# AD6645.net
KiCad netlist of a schematic drawn in Altium Designer
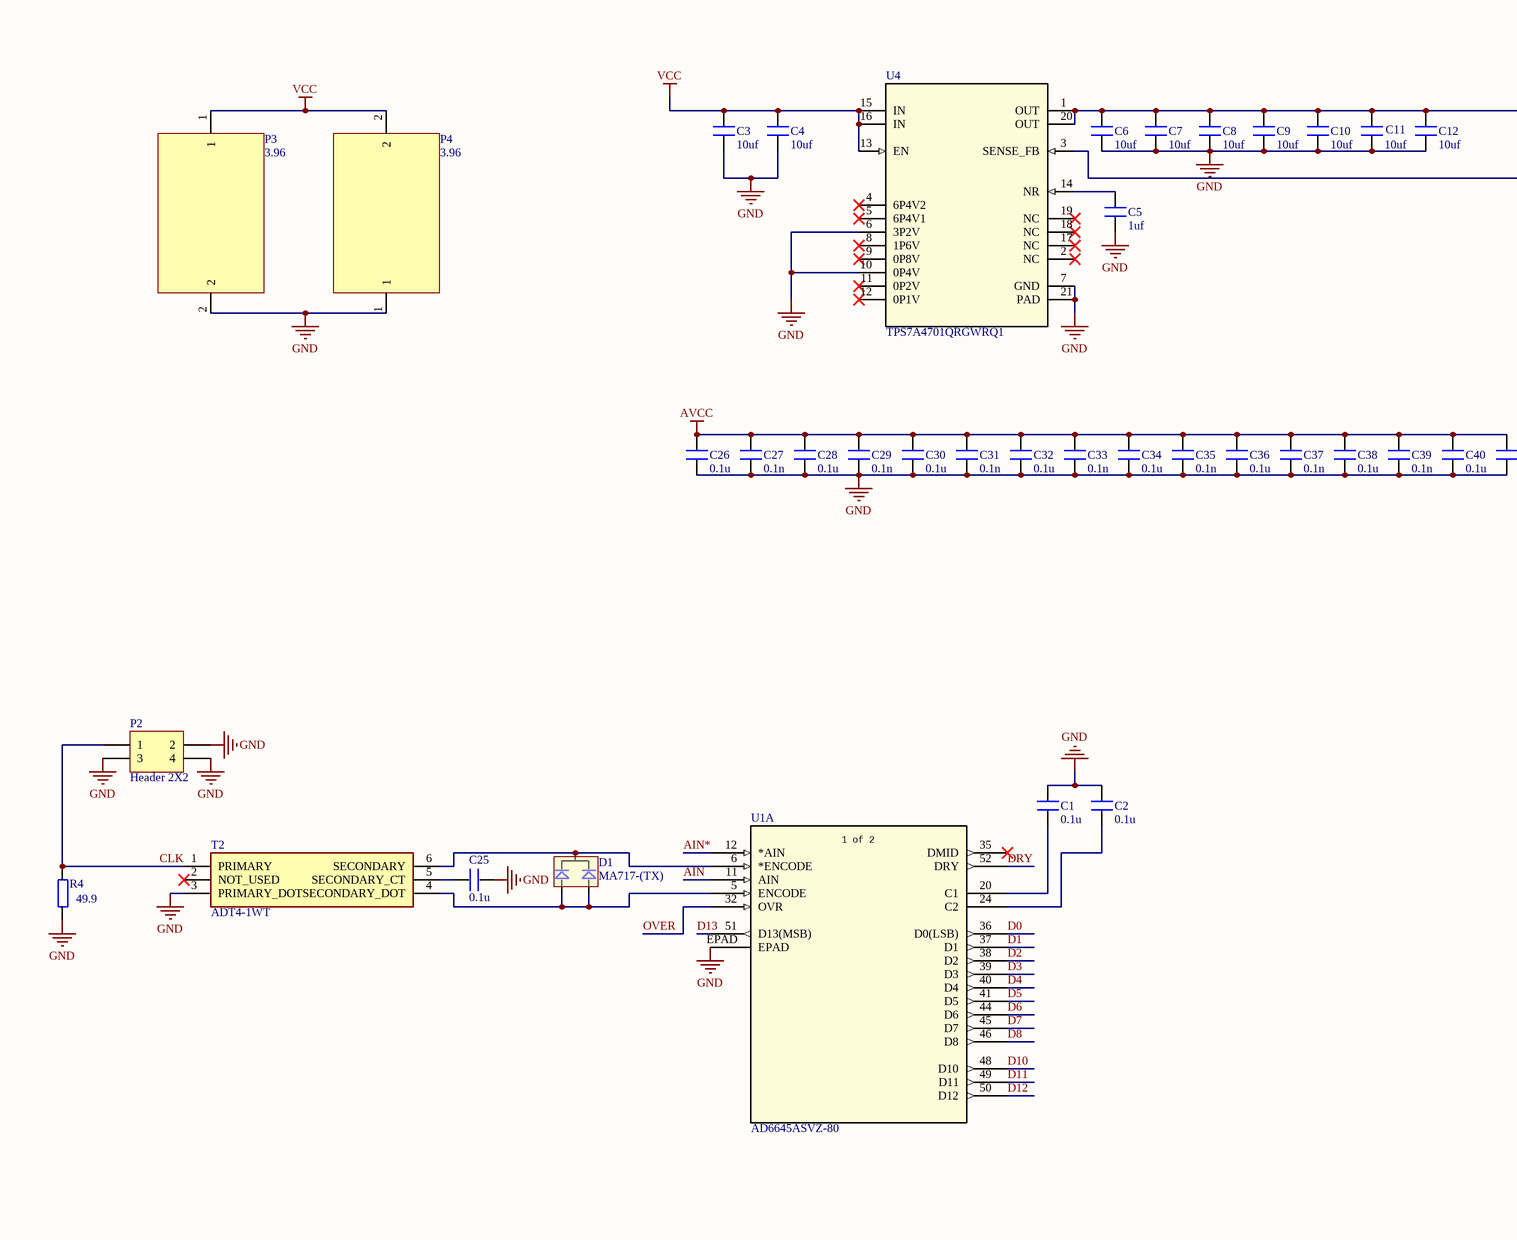
[diagram p0: AD6645.SchDoc, left]
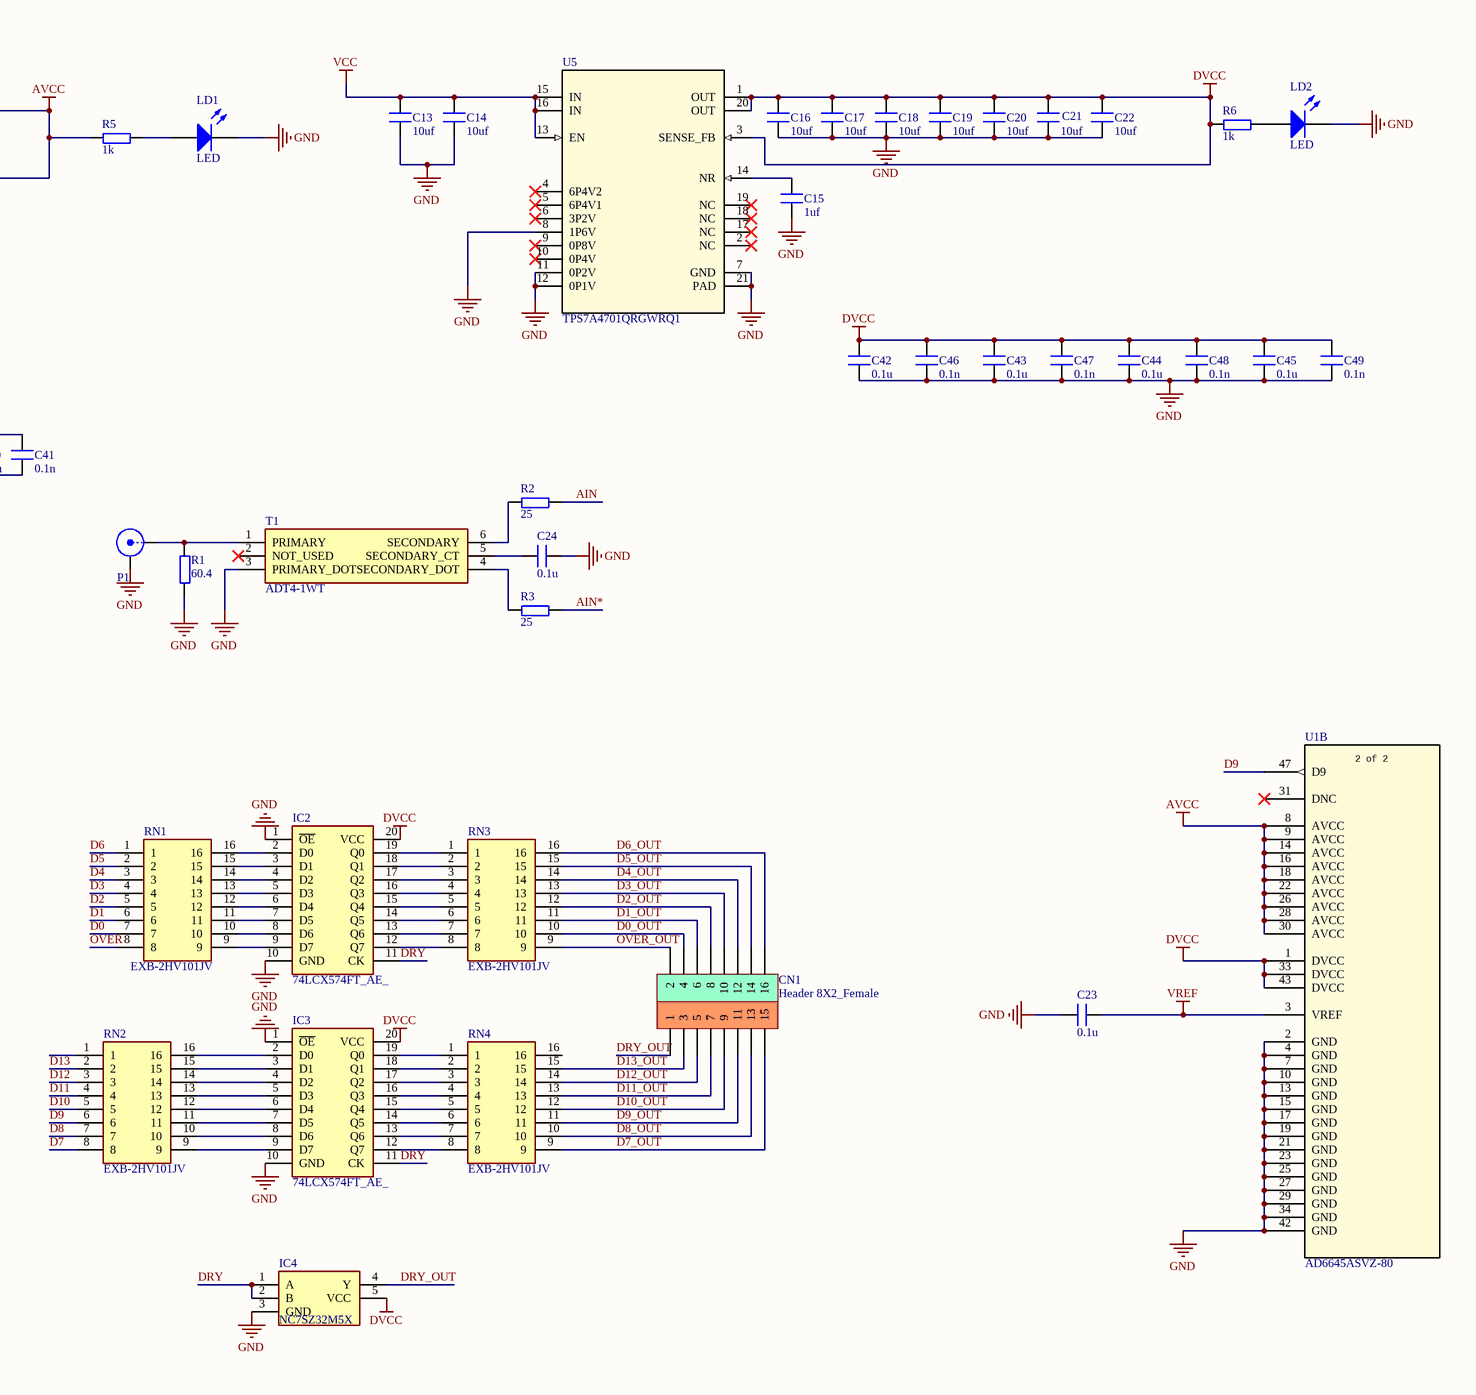
[diagram p1: AD6645.SchDoc, right]

(export (version "E")
  (design (tool "Eeschema 10.0.6"))
  (components
    (comp (ref "C1")
      (value "0.1u")
      (footprint "0402")
      (description "Capacitor")
      (libsource (lib "MYLIB") (part "C"))
    )
    (comp (ref "C2")
      (value "0.1u")
      (footprint "0402")
      (description "Capacitor")
      (libsource (lib "MYLIB") (part "C"))
    )
    (comp (ref "C3")
      (value "10uf")
      (footprint "0603C")
      (description "Capacitor")
      (libsource (lib "MYLIB") (part "C"))
    )
    (comp (ref "C4")
      (value "10uf")
      (footprint "0603C")
      (description "Capacitor")
      (libsource (lib "MYLIB") (part "C"))
    )
    (comp (ref "C5")
      (value "1uf")
      (footprint "0402")
      (description "Capacitor")
      (libsource (lib "MYLIB") (part "C"))
    )
    (comp (ref "C6")
      (value "10uf")
      (footprint "0603C")
      (description "Capacitor")
      (libsource (lib "MYLIB") (part "C"))
    )
    (comp (ref "C7")
      (value "10uf")
      (footprint "0603C")
      (description "Capacitor")
      (libsource (lib "MYLIB") (part "C"))
    )
    (comp (ref "C8")
      (value "10uf")
      (footprint "0603C")
      (description "Capacitor")
      (libsource (lib "MYLIB") (part "C"))
    )
    (comp (ref "C9")
      (value "10uf")
      (footprint "0603C")
      (description "Capacitor")
      (libsource (lib "MYLIB") (part "C"))
    )
    (comp (ref "C10")
      (value "10uf")
      (footprint "0603C")
      (description "Capacitor")
      (libsource (lib "MYLIB") (part "C"))
    )
    (comp (ref "C11")
      (value "10uf")
      (footprint "0603C")
      (description "Capacitor")
      (libsource (lib "MYLIB") (part "C"))
    )
    (comp (ref "C12")
      (value "10uf")
      (footprint "0603C")
      (description "Capacitor")
      (libsource (lib "MYLIB") (part "C"))
    )
    (comp (ref "C13")
      (value "10uf")
      (footprint "0603C")
      (description "Capacitor")
      (libsource (lib "MYLIB") (part "C"))
    )
    (comp (ref "C14")
      (value "10uf")
      (footprint "0603C")
      (description "Capacitor")
      (libsource (lib "MYLIB") (part "C"))
    )
    (comp (ref "C15")
      (value "1uf")
      (footprint "0402")
      (description "Capacitor")
      (libsource (lib "MYLIB") (part "C"))
    )
    (comp (ref "C16")
      (value "10uf")
      (footprint "0603C")
      (description "Capacitor")
      (libsource (lib "MYLIB") (part "C"))
    )
    (comp (ref "C17")
      (value "10uf")
      (footprint "0603C")
      (description "Capacitor")
      (libsource (lib "MYLIB") (part "C"))
    )
    (comp (ref "C18")
      (value "10uf")
      (footprint "0603C")
      (description "Capacitor")
      (libsource (lib "MYLIB") (part "C"))
    )
    (comp (ref "C19")
      (value "10uf")
      (footprint "0603C")
      (description "Capacitor")
      (libsource (lib "MYLIB") (part "C"))
    )
    (comp (ref "C20")
      (value "10uf")
      (footprint "0603C")
      (description "Capacitor")
      (libsource (lib "MYLIB") (part "C"))
    )
    (comp (ref "C21")
      (value "10uf")
      (footprint "0603C")
      (description "Capacitor")
      (libsource (lib "MYLIB") (part "C"))
    )
    (comp (ref "C22")
      (value "10uf")
      (footprint "0603C")
      (description "Capacitor")
      (libsource (lib "MYLIB") (part "C"))
    )
    (comp (ref "C23")
      (value "0.1u")
      (footprint "0402")
      (description "Capacitor")
      (libsource (lib "MYLIB") (part "C"))
    )
    (comp (ref "C24")
      (value "0.1u")
      (footprint "0603C")
      (description "Capacitor")
      (libsource (lib "MYLIB") (part "C"))
    )
    (comp (ref "C25")
      (value "0.1u")
      (footprint "0603C")
      (description "Capacitor")
      (libsource (lib "MYLIB") (part "C"))
    )
    (comp (ref "C26")
      (value "0.1u")
      (footprint "0402")
      (description "Capacitor")
      (libsource (lib "MYLIB") (part "C"))
    )
    (comp (ref "C27")
      (value "0.1n")
      (footprint "0402")
      (description "Capacitor")
      (libsource (lib "MYLIB") (part "C"))
    )
    (comp (ref "C28")
      (value "0.1u")
      (footprint "0402")
      (description "Capacitor")
      (libsource (lib "MYLIB") (part "C"))
    )
    (comp (ref "C29")
      (value "0.1n")
      (footprint "0402")
      (description "Capacitor")
      (libsource (lib "MYLIB") (part "C"))
    )
    (comp (ref "C30")
      (value "0.1u")
      (footprint "0402")
      (description "Capacitor")
      (libsource (lib "MYLIB") (part "C"))
    )
    (comp (ref "C31")
      (value "0.1n")
      (footprint "0402")
      (description "Capacitor")
      (libsource (lib "MYLIB") (part "C"))
    )
    (comp (ref "C32")
      (value "0.1u")
      (footprint "0402")
      (description "Capacitor")
      (libsource (lib "MYLIB") (part "C"))
    )
    (comp (ref "C33")
      (value "0.1n")
      (footprint "0402")
      (description "Capacitor")
      (libsource (lib "MYLIB") (part "C"))
    )
    (comp (ref "C34")
      (value "0.1u")
      (footprint "0402")
      (description "Capacitor")
      (libsource (lib "MYLIB") (part "C"))
    )
    (comp (ref "C35")
      (value "0.1n")
      (footprint "0402")
      (description "Capacitor")
      (libsource (lib "MYLIB") (part "C"))
    )
    (comp (ref "C36")
      (value "0.1u")
      (footprint "0402")
      (description "Capacitor")
      (libsource (lib "MYLIB") (part "C"))
    )
    (comp (ref "C37")
      (value "0.1n")
      (footprint "0402")
      (description "Capacitor")
      (libsource (lib "MYLIB") (part "C"))
    )
    (comp (ref "C38")
      (value "0.1u")
      (footprint "0402")
      (description "Capacitor")
      (libsource (lib "MYLIB") (part "C"))
    )
    (comp (ref "C39")
      (value "0.1n")
      (footprint "0402")
      (description "Capacitor")
      (libsource (lib "MYLIB") (part "C"))
    )
    (comp (ref "C40")
      (value "0.1u")
      (footprint "0402")
      (description "Capacitor")
      (libsource (lib "MYLIB") (part "C"))
    )
    (comp (ref "C41")
      (value "0.1n")
      (footprint "0402")
      (description "Capacitor")
      (libsource (lib "MYLIB") (part "C"))
    )
    (comp (ref "C42")
      (value "0.1u")
      (footprint "0402")
      (description "Capacitor")
      (libsource (lib "MYLIB") (part "C"))
    )
    (comp (ref "C43")
      (value "0.1u")
      (footprint "0402")
      (description "Capacitor")
      (libsource (lib "MYLIB") (part "C"))
    )
    (comp (ref "C44")
      (value "0.1u")
      (footprint "0402")
      (description "Capacitor")
      (libsource (lib "MYLIB") (part "C"))
    )
    (comp (ref "C45")
      (value "0.1u")
      (footprint "0402")
      (description "Capacitor")
      (libsource (lib "MYLIB") (part "C"))
    )
    (comp (ref "C46")
      (value "0.1n")
      (footprint "0402")
      (description "Capacitor")
      (libsource (lib "MYLIB") (part "C"))
    )
    (comp (ref "C47")
      (value "0.1n")
      (footprint "0402")
      (description "Capacitor")
      (libsource (lib "MYLIB") (part "C"))
    )
    (comp (ref "C48")
      (value "0.1n")
      (footprint "0402")
      (description "Capacitor")
      (libsource (lib "MYLIB") (part "C"))
    )
    (comp (ref "C49")
      (value "0.1n")
      (footprint "0402")
      (description "Capacitor")
      (libsource (lib "MYLIB") (part "C"))
    )
    (comp (ref "CN1")
      (value "Header 8X2_Female")
      (footprint "HDR_8x2_2R54_V_F")
      (description "Header, 8-Pin, Dual row,female")
      (fields (field (name "PUBLISHER") "Altium Limited"))
      (libsource (lib "MYLIB") (part "Header 8X2_Female"))
    )
    (comp (ref "D1")
      (value "MA717-(TX)")
      (footprint "SOT-23")
      (description "双肖特基二极管")
      (libsource (lib "MYLIB") (part "BAT54C"))
    )
    (comp (ref "IC2")
      (value "74LCX574FT_AE_")
      (footprint "MYLIB:SOP65P640X120-20N")
      (description "Integrated Circuit")
      (fields (field (name "MANUFACTURER_PART_NUMBER") "74LCX574FT(AE)"))
      (libsource (lib "*") (part "74LCX574FT_AE_"))
    )
    (comp (ref "IC3")
      (value "74LCX574FT_AE_")
      (footprint "MYLIB:SOP65P640X120-20N")
      (description "Integrated Circuit")
      (fields (field (name "MANUFACTURER_PART_NUMBER") "74LCX574FT(AE)"))
      (libsource (lib "MYLIB") (part "74LCX574FT_AE_"))
    )
    (comp (ref "IC4")
      (value "NC7SZ32M5X")
      (footprint "MYLIB:SOT95P280X145-5N")
      (description "Integrated Circuit")
      (fields (field (name "MOUSER PART NUMBER") "512-NC7SZ32M5X"))
      (libsource (lib "*") (part "NC7SZ32M5X"))
    )
    (comp (ref "LD1")
      (value "LED")
      (footprint "SMDLED")
      (description "Typical RED, GREEN, YELLOW, AMBER GaAs LED")
      (fields (field (name "PUBLISHER") "Altium Limited"))
      (libsource (lib "MYLIB") (part "LED"))
    )
    (comp (ref "LD2")
      (value "LED")
      (footprint "SMDLED")
      (description "Typical RED, GREEN, YELLOW, AMBER GaAs LED")
      (fields (field (name "PUBLISHER") "Altium Limited"))
      (libsource (lib "MYLIB") (part "LED"))
    )
    (comp (ref "P1")
      (value "SMA")
      (footprint "SMA")
      (description "SMA Connector")
      (libsource (lib "MYLIB") (part "SMA"))
    )
    (comp (ref "P2")
      (value "Header 2X2")
      (footprint "HDR2X2")
      (description "Header, 2-Pin, Dual row")
      (fields (field (name "PUBLISHER") "Altium Limited"))
      (libsource (lib "MYLIB") (part "Header 2X2"))
    )
    (comp (ref "P3") (value "3.96") (footprint "3.96") (libsource (lib "MYLIB") (part "3.96")))
    (comp (ref "P4") (value "3.96") (footprint "3.96") (libsource (lib "") (part "3.96_1")))
    (comp (ref "R1")
      (value "60.4")
      (footprint "0603R")
      (description "Resistor")
      (libsource (lib "MYLIB") (part "Resistor"))
    )
    (comp (ref "R2")
      (value "25")
      (footprint "0603R")
      (description "Resistor")
      (libsource (lib "MYLIB") (part "Resistor"))
    )
    (comp (ref "R3")
      (value "25")
      (footprint "0603R")
      (description "Resistor")
      (libsource (lib "MYLIB") (part "Resistor"))
    )
    (comp (ref "R4")
      (value "49.9")
      (footprint "0603R")
      (description "Resistor")
      (libsource (lib "MYLIB") (part "Resistor"))
    )
    (comp (ref "R5")
      (value "1k")
      (footprint "0603R")
      (description "Resistor")
      (libsource (lib "MYLIB") (part "Resistor"))
    )
    (comp (ref "R6")
      (value "1k")
      (footprint "0603R")
      (description "Resistor")
      (libsource (lib "MYLIB") (part "Resistor"))
    )
    (comp (ref "RN1")
      (value "EXB-2HV101JV")
      (footprint "MYLIB:EXB2HV101JV")
      (description "Resistor Network")
      (fields (field (name "MOUSER PART NUMBER") "667-EXB-2HV101JV"))
      (libsource (lib "*") (part "EXB-2HV101JV"))
    )
    (comp (ref "RN2")
      (value "EXB-2HV101JV")
      (footprint "MYLIB:EXB2HV101JV")
      (description "Resistor Network")
      (fields (field (name "MOUSER PART NUMBER") "667-EXB-2HV101JV"))
      (libsource (lib "MYLIB") (part "EXB-2HV101JV"))
    )
    (comp (ref "RN3")
      (value "EXB-2HV101JV")
      (footprint "MYLIB:EXB2HV101JV")
      (description "Resistor Network")
      (fields (field (name "MOUSER PART NUMBER") "667-EXB-2HV101JV"))
      (libsource (lib "MYLIB") (part "EXB-2HV101JV"))
    )
    (comp (ref "RN4")
      (value "EXB-2HV101JV")
      (footprint "MYLIB:EXB2HV101JV")
      (description "Resistor Network")
      (fields (field (name "MOUSER PART NUMBER") "667-EXB-2HV101JV"))
      (libsource (lib "MYLIB") (part "EXB-2HV101JV"))
    )
    (comp (ref "T1")
      (value "ADT4-1WT")
      (footprint "MYLIB:ADT41WT")
      (description "Transformer")
      (libsource (lib "*") (part "ADT4-1WT"))
    )
    (comp (ref "T2")
      (value "ADT4-1WT")
      (footprint "MYLIB:ADT41WT")
      (description "Transformer")
      (libsource (lib "MYLIB") (part "ADT4-1WT"))
    )
    (comp (ref "U1")
      (value "AD6645ASVZ-80")
      (footprint "SV_52_1_ADI")
      (description "No Description Available")
      (fields (field (name "COPYRIGHT") "Copyright (C) 2021 Accelerated Designs. All rights reserved"))
      (libsource (lib "MYLIB") (part "AD6645ASVZ-80"))
    )
    (comp (ref "U4")
      (value "TPS7A4701QRGWRQ1")
      (footprint "RGW0020A")
      (description "No Description Available")
      (fields
        (field (name "MANUFACTURER") "Texas Instruments")
        (field (name "COPYRIGHT") "Copyright (C) 2018 Accelerated Designs. All rights reserved")
      )
      (libsource (lib "MYLIB") (part "TPS7A4701QRGWRQ1"))
    )
    (comp (ref "U5")
      (value "TPS7A4701QRGWRQ1")
      (footprint "RGW0020A")
      (description "No Description Available")
      (fields
        (field (name "MANUFACTURER") "Texas Instruments")
        (field (name "COPYRIGHT") "Copyright (C) 2018 Accelerated Designs. All rights reserved")
      )
      (libsource (lib "MYLIB") (part "TPS7A4701QRGWRQ1"))
    )
  )
  (nets
    (net (code "1") (name "/AIN") (class "Default")
      (node (ref "R2") (pin "2") (pintype "passive"))
      (node (ref "U1") (pin "11") (pinfunction "AIN_11") (pintype "input"))
    )
    (net (code "2") (name "/AIN*") (class "Default")
      (node (ref "R3") (pin "2") (pintype "passive"))
      (node (ref "U1") (pin "12") (pinfunction "*AIN_12") (pintype "input"))
    )
    (net (code "3") (name "/CLK") (class "Default")
      (node (ref "P2") (pin "1") (pinfunction "1_1") (pintype "passive"))
      (node (ref "R4") (pin "2") (pintype "passive"))
      (node (ref "T2") (pin "1") (pinfunction "PRIMARY_1") (pintype "passive"))
    )
    (net (code "4") (name "/D0") (class "Default")
      (node (ref "RN1") (pin "7") (pinfunction "7_7") (pintype "passive"))
      (node (ref "U1") (pin "36") (pinfunction "D0(LSB)_36") (pintype "output"))
    )
    (net (code "5") (name "/D0_OUT") (class "Default")
      (node (ref "CN1") (pin "4") (pinfunction "4_4") (pintype "passive"))
      (node (ref "RN3") (pin "10") (pinfunction "10_10") (pintype "passive"))
    )
    (net (code "6") (name "/D1") (class "Default")
      (node (ref "RN1") (pin "6") (pinfunction "6_6") (pintype "passive"))
      (node (ref "U1") (pin "37") (pinfunction "D1_37") (pintype "output"))
    )
    (net (code "7") (name "/D1_OUT") (class "Default")
      (node (ref "CN1") (pin "6") (pinfunction "6_6") (pintype "passive"))
      (node (ref "RN3") (pin "11") (pinfunction "11_11") (pintype "passive"))
    )
    (net (code "8") (name "/D2") (class "Default")
      (node (ref "RN1") (pin "5") (pinfunction "5_5") (pintype "passive"))
      (node (ref "U1") (pin "38") (pinfunction "D2_38") (pintype "output"))
    )
    (net (code "9") (name "/D2_OUT") (class "Default")
      (node (ref "CN1") (pin "8") (pinfunction "8_8") (pintype "passive"))
      (node (ref "RN3") (pin "12") (pinfunction "12_12") (pintype "passive"))
    )
    (net (code "10") (name "/D3") (class "Default")
      (node (ref "RN1") (pin "4") (pinfunction "4_4") (pintype "passive"))
      (node (ref "U1") (pin "39") (pinfunction "D3_39") (pintype "output"))
    )
    (net (code "11") (name "/D3_OUT") (class "Default")
      (node (ref "CN1") (pin "10") (pinfunction "10_10") (pintype "passive"))
      (node (ref "RN3") (pin "13") (pinfunction "13_13") (pintype "passive"))
    )
    (net (code "12") (name "/D4") (class "Default")
      (node (ref "RN1") (pin "3") (pinfunction "3_3") (pintype "passive"))
      (node (ref "U1") (pin "40") (pinfunction "D4_40") (pintype "output"))
    )
    (net (code "13") (name "/D4_OUT") (class "Default")
      (node (ref "CN1") (pin "12") (pinfunction "12_12") (pintype "passive"))
      (node (ref "RN3") (pin "14") (pinfunction "14_14") (pintype "passive"))
    )
    (net (code "14") (name "/D5") (class "Default")
      (node (ref "RN1") (pin "2") (pinfunction "2_2") (pintype "passive"))
      (node (ref "U1") (pin "41") (pinfunction "D5_41") (pintype "output"))
    )
    (net (code "15") (name "/D5_OUT") (class "Default")
      (node (ref "CN1") (pin "14") (pinfunction "14_14") (pintype "passive"))
      (node (ref "RN3") (pin "15") (pinfunction "15_15") (pintype "passive"))
    )
    (net (code "16") (name "/D6") (class "Default")
      (node (ref "RN1") (pin "1") (pinfunction "1_1") (pintype "passive"))
      (node (ref "U1") (pin "44") (pinfunction "D6_44") (pintype "output"))
    )
    (net (code "17") (name "/D6_OUT") (class "Default")
      (node (ref "CN1") (pin "16") (pinfunction "16_16") (pintype "passive"))
      (node (ref "RN3") (pin "16") (pinfunction "16_16") (pintype "passive"))
    )
    (net (code "18") (name "/D7") (class "Default")
      (node (ref "RN2") (pin "8") (pinfunction "8_8") (pintype "passive"))
      (node (ref "U1") (pin "45") (pinfunction "D7_45") (pintype "output"))
    )
    (net (code "19") (name "/D7_OUT") (class "Default")
      (node (ref "CN1") (pin "15") (pinfunction "15_15") (pintype "passive"))
      (node (ref "RN4") (pin "9") (pinfunction "9_9") (pintype "passive"))
    )
    (net (code "20") (name "/D8") (class "Default")
      (node (ref "RN2") (pin "7") (pinfunction "7_7") (pintype "passive"))
      (node (ref "U1") (pin "46") (pinfunction "D8_46") (pintype "output"))
    )
    (net (code "21") (name "/D8_OUT") (class "Default")
      (node (ref "CN1") (pin "13") (pinfunction "13_13") (pintype "passive"))
      (node (ref "RN4") (pin "10") (pinfunction "10_10") (pintype "passive"))
    )
    (net (code "22") (name "/D9") (class "Default")
      (node (ref "RN2") (pin "6") (pinfunction "6_6") (pintype "passive"))
      (node (ref "U1") (pin "47") (pinfunction "D9_47") (pintype "output"))
    )
    (net (code "23") (name "/D9_OUT") (class "Default")
      (node (ref "CN1") (pin "11") (pinfunction "11_11") (pintype "passive"))
      (node (ref "RN4") (pin "11") (pinfunction "11_11") (pintype "passive"))
    )
    (net (code "24") (name "/D10") (class "Default")
      (node (ref "RN2") (pin "5") (pinfunction "5_5") (pintype "passive"))
      (node (ref "U1") (pin "48") (pinfunction "D10_48") (pintype "output"))
    )
    (net (code "25") (name "/D10_OUT") (class "Default")
      (node (ref "CN1") (pin "9") (pinfunction "9_9") (pintype "passive"))
      (node (ref "RN4") (pin "12") (pinfunction "12_12") (pintype "passive"))
    )
    (net (code "26") (name "/D11") (class "Default")
      (node (ref "RN2") (pin "4") (pinfunction "4_4") (pintype "passive"))
      (node (ref "U1") (pin "49") (pinfunction "D11_49") (pintype "output"))
    )
    (net (code "27") (name "/D11_OUT") (class "Default")
      (node (ref "CN1") (pin "7") (pinfunction "7_7") (pintype "passive"))
      (node (ref "RN4") (pin "13") (pinfunction "13_13") (pintype "passive"))
    )
    (net (code "28") (name "/D12") (class "Default")
      (node (ref "RN2") (pin "3") (pinfunction "3_3") (pintype "passive"))
      (node (ref "U1") (pin "50") (pinfunction "D12_50") (pintype "output"))
    )
    (net (code "29") (name "/D12_OUT") (class "Default")
      (node (ref "CN1") (pin "5") (pinfunction "5_5") (pintype "passive"))
      (node (ref "RN4") (pin "14") (pinfunction "14_14") (pintype "passive"))
    )
    (net (code "30") (name "/D13") (class "Default")
      (node (ref "RN2") (pin "2") (pinfunction "2_2") (pintype "passive"))
      (node (ref "U1") (pin "51") (pinfunction "D13(MSB)_51") (pintype "output"))
    )
    (net (code "31") (name "/D13_OUT") (class "Default")
      (node (ref "CN1") (pin "3") (pinfunction "3_3") (pintype "passive"))
      (node (ref "RN4") (pin "15") (pinfunction "15_15") (pintype "passive"))
    )
    (net (code "32") (name "/DRY") (class "Default")
      (node (ref "IC2") (pin "11") (pinfunction "CK_11") (pintype "passive"))
      (node (ref "IC3") (pin "11") (pinfunction "CK_11") (pintype "passive"))
      (node (ref "IC4") (pin "1") (pinfunction "A_1") (pintype "passive"))
      (node (ref "IC4") (pin "2") (pinfunction "B_2") (pintype "passive"))
      (node (ref "U1") (pin "52") (pinfunction "DRY_52") (pintype "output"))
    )
    (net (code "33") (name "/DRY_OUT") (class "Default")
      (node (ref "CN1") (pin "1") (pinfunction "1_1") (pintype "passive"))
      (node (ref "IC4") (pin "4") (pinfunction "Y_4") (pintype "passive"))
    )
    (net (code "34") (name "/OVER") (class "Default")
      (node (ref "RN1") (pin "8") (pinfunction "8_8") (pintype "passive"))
      (node (ref "U1") (pin "32") (pinfunction "OVR_32") (pintype "input"))
    )
    (net (code "35") (name "/OVER_OUT") (class "Default")
      (node (ref "CN1") (pin "2") (pinfunction "2_2") (pintype "passive"))
      (node (ref "RN3") (pin "9") (pinfunction "9_9") (pintype "passive"))
    )
    (net (code "36") (name "AVCC") (class "Default")
      (node (ref "C10") (pin "2") (pintype "passive"))
      (node (ref "C11") (pin "2") (pintype "passive"))
      (node (ref "C12") (pin "2") (pintype "passive"))
      (node (ref "C26") (pin "2") (pintype "passive"))
      (node (ref "C27") (pin "2") (pintype "passive"))
      (node (ref "C28") (pin "2") (pintype "passive"))
      (node (ref "C29") (pin "2") (pintype "passive"))
      (node (ref "C30") (pin "2") (pintype "passive"))
      (node (ref "C31") (pin "2") (pintype "passive"))
      (node (ref "C32") (pin "2") (pintype "passive"))
      (node (ref "C33") (pin "2") (pintype "passive"))
      (node (ref "C34") (pin "2") (pintype "passive"))
      (node (ref "C35") (pin "2") (pintype "passive"))
      (node (ref "C36") (pin "2") (pintype "passive"))
      (node (ref "C37") (pin "2") (pintype "passive"))
      (node (ref "C38") (pin "2") (pintype "passive"))
      (node (ref "C39") (pin "2") (pintype "passive"))
      (node (ref "C40") (pin "2") (pintype "passive"))
      (node (ref "C41") (pin "2") (pintype "passive"))
      (node (ref "C6") (pin "2") (pintype "passive"))
      (node (ref "C7") (pin "2") (pintype "passive"))
      (node (ref "C8") (pin "2") (pintype "passive"))
      (node (ref "C9") (pin "2") (pintype "passive"))
      (node (ref "R5") (pin "1") (pintype "passive"))
      (node (ref "U1") (pin "14") (pinfunction "AVCC_14") (pintype "power_in"))
      (node (ref "U1") (pin "16") (pinfunction "AVCC_16") (pintype "power_in"))
      (node (ref "U1") (pin "18") (pinfunction "AVCC_18") (pintype "power_in"))
      (node (ref "U1") (pin "22") (pinfunction "AVCC_22") (pintype "power_in"))
      (node (ref "U1") (pin "26") (pinfunction "AVCC_26") (pintype "power_in"))
      (node (ref "U1") (pin "28") (pinfunction "AVCC_28") (pintype "power_in"))
      (node (ref "U1") (pin "30") (pinfunction "AVCC_30") (pintype "power_in"))
      (node (ref "U1") (pin "8") (pinfunction "AVCC_8") (pintype "power_in"))
      (node (ref "U1") (pin "9") (pinfunction "AVCC_9") (pintype "power_in"))
      (node (ref "U4") (pin "1") (pinfunction "OUT_1") (pintype "power_in"))
      (node (ref "U4") (pin "20") (pinfunction "OUT_20") (pintype "power_in"))
      (node (ref "U4") (pin "3") (pinfunction "SENSE_FB_3") (pintype "input"))
    )
    (net (code "37") (name "DVCC") (class "Default")
      (node (ref "C16") (pin "2") (pintype "passive"))
      (node (ref "C17") (pin "2") (pintype "passive"))
      (node (ref "C18") (pin "2") (pintype "passive"))
      (node (ref "C19") (pin "2") (pintype "passive"))
      (node (ref "C20") (pin "2") (pintype "passive"))
      (node (ref "C21") (pin "2") (pintype "passive"))
      (node (ref "C22") (pin "2") (pintype "passive"))
      (node (ref "C42") (pin "2") (pintype "passive"))
      (node (ref "C43") (pin "2") (pintype "passive"))
      (node (ref "C44") (pin "2") (pintype "passive"))
      (node (ref "C45") (pin "2") (pintype "passive"))
      (node (ref "C46") (pin "2") (pintype "passive"))
      (node (ref "C47") (pin "2") (pintype "passive"))
      (node (ref "C48") (pin "2") (pintype "passive"))
      (node (ref "C49") (pin "2") (pintype "passive"))
      (node (ref "IC2") (pin "20") (pinfunction "VCC_20") (pintype "passive"))
      (node (ref "IC3") (pin "20") (pinfunction "VCC_20") (pintype "passive"))
      (node (ref "IC4") (pin "5") (pinfunction "VCC_5") (pintype "power_in"))
      (node (ref "R6") (pin "1") (pintype "passive"))
      (node (ref "U1") (pin "1") (pinfunction "DVCC_1") (pintype "power_in"))
      (node (ref "U1") (pin "33") (pinfunction "DVCC_33") (pintype "power_in"))
      (node (ref "U1") (pin "43") (pinfunction "DVCC_43") (pintype "power_in"))
      (node (ref "U5") (pin "1") (pinfunction "OUT_1") (pintype "power_in"))
      (node (ref "U5") (pin "20") (pinfunction "OUT_20") (pintype "power_in"))
      (node (ref "U5") (pin "3") (pinfunction "SENSE_FB_3") (pintype "input"))
    )
    (net (code "38") (name "GND") (class "Default")
      (node (ref "C1") (pin "2") (pintype "passive"))
      (node (ref "C10") (pin "1") (pintype "passive"))
      (node (ref "C11") (pin "1") (pintype "passive"))
      (node (ref "C12") (pin "1") (pintype "passive"))
      (node (ref "C13") (pin "1") (pintype "passive"))
      (node (ref "C14") (pin "1") (pintype "passive"))
      (node (ref "C15") (pin "1") (pintype "passive"))
      (node (ref "C16") (pin "1") (pintype "passive"))
      (node (ref "C17") (pin "1") (pintype "passive"))
      (node (ref "C18") (pin "1") (pintype "passive"))
      (node (ref "C19") (pin "1") (pintype "passive"))
      (node (ref "C2") (pin "2") (pintype "passive"))
      (node (ref "C20") (pin "1") (pintype "passive"))
      (node (ref "C21") (pin "1") (pintype "passive"))
      (node (ref "C22") (pin "1") (pintype "passive"))
      (node (ref "C23") (pin "1") (pintype "passive"))
      (node (ref "C24") (pin "2") (pintype "passive"))
      (node (ref "C25") (pin "2") (pintype "passive"))
      (node (ref "C26") (pin "1") (pintype "passive"))
      (node (ref "C27") (pin "1") (pintype "passive"))
      (node (ref "C28") (pin "1") (pintype "passive"))
      (node (ref "C29") (pin "1") (pintype "passive"))
      (node (ref "C3") (pin "1") (pintype "passive"))
      (node (ref "C30") (pin "1") (pintype "passive"))
      (node (ref "C31") (pin "1") (pintype "passive"))
      (node (ref "C32") (pin "1") (pintype "passive"))
      (node (ref "C33") (pin "1") (pintype "passive"))
      (node (ref "C34") (pin "1") (pintype "passive"))
      (node (ref "C35") (pin "1") (pintype "passive"))
      (node (ref "C36") (pin "1") (pintype "passive"))
      (node (ref "C37") (pin "1") (pintype "passive"))
      (node (ref "C38") (pin "1") (pintype "passive"))
      (node (ref "C39") (pin "1") (pintype "passive"))
      (node (ref "C4") (pin "1") (pintype "passive"))
      (node (ref "C40") (pin "1") (pintype "passive"))
      (node (ref "C41") (pin "1") (pintype "passive"))
      (node (ref "C42") (pin "1") (pintype "passive"))
      (node (ref "C43") (pin "1") (pintype "passive"))
      (node (ref "C44") (pin "1") (pintype "passive"))
      (node (ref "C45") (pin "1") (pintype "passive"))
      (node (ref "C46") (pin "1") (pintype "passive"))
      (node (ref "C47") (pin "1") (pintype "passive"))
      (node (ref "C48") (pin "1") (pintype "passive"))
      (node (ref "C49") (pin "1") (pintype "passive"))
      (node (ref "C5") (pin "1") (pintype "passive"))
      (node (ref "C6") (pin "1") (pintype "passive"))
      (node (ref "C7") (pin "1") (pintype "passive"))
      (node (ref "C8") (pin "1") (pintype "passive"))
      (node (ref "C9") (pin "1") (pintype "passive"))
      (node (ref "IC2") (pin "1") (pinfunction "~{OE}_1") (pintype "passive"))
      (node (ref "IC2") (pin "10") (pinfunction "GND_10") (pintype "passive"))
      (node (ref "IC3") (pin "1") (pinfunction "~{OE}_1") (pintype "passive"))
      (node (ref "IC3") (pin "10") (pinfunction "GND_10") (pintype "passive"))
      (node (ref "IC4") (pin "3") (pinfunction "GND_3") (pintype "power_in"))
      (node (ref "LD1") (pin "2") (pinfunction "K_2") (pintype "passive"))
      (node (ref "LD2") (pin "2") (pinfunction "K_2") (pintype "passive"))
      (node (ref "P1") (pin "2") (pinfunction "Y_2") (pintype "passive"))
      (node (ref "P2") (pin "2") (pinfunction "2_2") (pintype "passive"))
      (node (ref "P2") (pin "3") (pinfunction "3_3") (pintype "passive"))
      (node (ref "P2") (pin "4") (pinfunction "4_4") (pintype "passive"))
      (node (ref "P3") (pin "2") (pinfunction "2_2") (pintype "passive"))
      (node (ref "P4") (pin "1") (pinfunction "1_1") (pintype "passive"))
      (node (ref "R1") (pin "1") (pintype "passive"))
      (node (ref "R4") (pin "1") (pintype "passive"))
      (node (ref "T1") (pin "3") (pinfunction "PRIMARY_DOT_3") (pintype "passive"))
      (node (ref "T2") (pin "3") (pinfunction "PRIMARY_DOT_3") (pintype "passive"))
      (node (ref "U1") (pin "10") (pinfunction "GND_10") (pintype "power_in"))
      (node (ref "U1") (pin "13") (pinfunction "GND_13") (pintype "power_in"))
      (node (ref "U1") (pin "15") (pinfunction "GND_15") (pintype "power_in"))
      (node (ref "U1") (pin "17") (pinfunction "GND_17") (pintype "power_in"))
      (node (ref "U1") (pin "19") (pinfunction "GND_19") (pintype "power_in"))
      (node (ref "U1") (pin "2") (pinfunction "GND_2") (pintype "power_in"))
      (node (ref "U1") (pin "21") (pinfunction "GND_21") (pintype "power_in"))
      (node (ref "U1") (pin "23") (pinfunction "GND_23") (pintype "power_in"))
      (node (ref "U1") (pin "25") (pinfunction "GND_25") (pintype "power_in"))
      (node (ref "U1") (pin "27") (pinfunction "GND_27") (pintype "power_in"))
      (node (ref "U1") (pin "29") (pinfunction "GND_29") (pintype "power_in"))
      (node (ref "U1") (pin "34") (pinfunction "GND_34") (pintype "power_in"))
      (node (ref "U1") (pin "4") (pinfunction "GND_4") (pintype "power_in"))
      (node (ref "U1") (pin "42") (pinfunction "GND_42") (pintype "power_in"))
      (node (ref "U1") (pin "7") (pinfunction "GND_7") (pintype "power_in"))
      (node (ref "U1") (pin "EPAD") (pinfunction "EPAD_EPAD") (pintype "passive"))
      (node (ref "U4") (pin "10") (pinfunction "0P4V_10") (pintype "passive"))
      (node (ref "U4") (pin "21") (pinfunction "PAD_21") (pintype "passive"))
      (node (ref "U4") (pin "6") (pinfunction "3P2V_6") (pintype "passive"))
      (node (ref "U4") (pin "7") (pinfunction "GND_7") (pintype "power_in"))
      (node (ref "U5") (pin "11") (pinfunction "0P2V_11") (pintype "passive"))
      (node (ref "U5") (pin "12") (pinfunction "0P1V_12") (pintype "passive"))
      (node (ref "U5") (pin "21") (pinfunction "PAD_21") (pintype "passive"))
      (node (ref "U5") (pin "7") (pinfunction "GND_7") (pintype "power_in"))
      (node (ref "U5") (pin "8") (pinfunction "1P6V_8") (pintype "passive"))
    )
    (net (code "39") (name "Net-(IC2-D0)") (class "Default")
      (node (ref "IC2") (pin "2") (pinfunction "D0_2") (pintype "passive"))
      (node (ref "RN1") (pin "16") (pinfunction "16_16") (pintype "passive"))
    )
    (net (code "40") (name "Net-(IC2-D1)") (class "Default")
      (node (ref "IC2") (pin "3") (pinfunction "D1_3") (pintype "passive"))
      (node (ref "RN1") (pin "15") (pinfunction "15_15") (pintype "passive"))
    )
    (net (code "41") (name "Net-(IC2-D2)") (class "Default")
      (node (ref "IC2") (pin "4") (pinfunction "D2_4") (pintype "passive"))
      (node (ref "RN1") (pin "14") (pinfunction "14_14") (pintype "passive"))
    )
    (net (code "42") (name "Net-(IC2-D3)") (class "Default")
      (node (ref "IC2") (pin "5") (pinfunction "D3_5") (pintype "passive"))
      (node (ref "RN1") (pin "13") (pinfunction "13_13") (pintype "passive"))
    )
    (net (code "43") (name "Net-(IC2-D4)") (class "Default")
      (node (ref "IC2") (pin "6") (pinfunction "D4_6") (pintype "passive"))
      (node (ref "RN1") (pin "12") (pinfunction "12_12") (pintype "passive"))
    )
    (net (code "44") (name "Net-(IC2-D5)") (class "Default")
      (node (ref "IC2") (pin "7") (pinfunction "D5_7") (pintype "passive"))
      (node (ref "RN1") (pin "11") (pinfunction "11_11") (pintype "passive"))
    )
    (net (code "45") (name "Net-(IC2-D6)") (class "Default")
      (node (ref "IC2") (pin "8") (pinfunction "D6_8") (pintype "passive"))
      (node (ref "RN1") (pin "10") (pinfunction "10_10") (pintype "passive"))
    )
    (net (code "46") (name "Net-(IC2-D7)") (class "Default")
      (node (ref "IC2") (pin "9") (pinfunction "D7_9") (pintype "passive"))
      (node (ref "RN1") (pin "9") (pinfunction "9_9") (pintype "passive"))
    )
    (net (code "47") (name "Net-(IC2-Q0)") (class "Default")
      (node (ref "IC2") (pin "19") (pinfunction "Q0_19") (pintype "passive"))
      (node (ref "RN3") (pin "1") (pinfunction "1_1") (pintype "passive"))
    )
    (net (code "48") (name "Net-(IC2-Q1)") (class "Default")
      (node (ref "IC2") (pin "18") (pinfunction "Q1_18") (pintype "passive"))
      (node (ref "RN3") (pin "2") (pinfunction "2_2") (pintype "passive"))
    )
    (net (code "49") (name "Net-(IC2-Q2)") (class "Default")
      (node (ref "IC2") (pin "17") (pinfunction "Q2_17") (pintype "passive"))
      (node (ref "RN3") (pin "3") (pinfunction "3_3") (pintype "passive"))
    )
    (net (code "50") (name "Net-(IC2-Q3)") (class "Default")
      (node (ref "IC2") (pin "16") (pinfunction "Q3_16") (pintype "passive"))
      (node (ref "RN3") (pin "4") (pinfunction "4_4") (pintype "passive"))
    )
    (net (code "51") (name "Net-(IC2-Q4)") (class "Default")
      (node (ref "IC2") (pin "15") (pinfunction "Q4_15") (pintype "passive"))
      (node (ref "RN3") (pin "5") (pinfunction "5_5") (pintype "passive"))
    )
    (net (code "52") (name "Net-(IC2-Q5)") (class "Default")
      (node (ref "IC2") (pin "14") (pinfunction "Q5_14") (pintype "passive"))
      (node (ref "RN3") (pin "6") (pinfunction "6_6") (pintype "passive"))
    )
    (net (code "53") (name "Net-(IC2-Q6)") (class "Default")
      (node (ref "IC2") (pin "13") (pinfunction "Q6_13") (pintype "passive"))
      (node (ref "RN3") (pin "7") (pinfunction "7_7") (pintype "passive"))
    )
    (net (code "54") (name "Net-(IC2-Q7)") (class "Default")
      (node (ref "IC2") (pin "12") (pinfunction "Q7_12") (pintype "passive"))
      (node (ref "RN3") (pin "8") (pinfunction "8_8") (pintype "passive"))
    )
    (net (code "55") (name "Net-(IC3-D0)") (class "Default")
      (node (ref "IC3") (pin "2") (pinfunction "D0_2") (pintype "passive"))
      (node (ref "RN2") (pin "16") (pinfunction "16_16") (pintype "passive"))
    )
    (net (code "56") (name "Net-(IC3-D1)") (class "Default")
      (node (ref "IC3") (pin "3") (pinfunction "D1_3") (pintype "passive"))
      (node (ref "RN2") (pin "15") (pinfunction "15_15") (pintype "passive"))
    )
    (net (code "57") (name "Net-(IC3-D2)") (class "Default")
      (node (ref "IC3") (pin "4") (pinfunction "D2_4") (pintype "passive"))
      (node (ref "RN2") (pin "14") (pinfunction "14_14") (pintype "passive"))
    )
    (net (code "58") (name "Net-(IC3-D3)") (class "Default")
      (node (ref "IC3") (pin "5") (pinfunction "D3_5") (pintype "passive"))
      (node (ref "RN2") (pin "13") (pinfunction "13_13") (pintype "passive"))
    )
    (net (code "59") (name "Net-(IC3-D4)") (class "Default")
      (node (ref "IC3") (pin "6") (pinfunction "D4_6") (pintype "passive"))
      (node (ref "RN2") (pin "12") (pinfunction "12_12") (pintype "passive"))
    )
    (net (code "60") (name "Net-(IC3-D5)") (class "Default")
      (node (ref "IC3") (pin "7") (pinfunction "D5_7") (pintype "passive"))
      (node (ref "RN2") (pin "11") (pinfunction "11_11") (pintype "passive"))
    )
    (net (code "61") (name "Net-(IC3-D6)") (class "Default")
      (node (ref "IC3") (pin "8") (pinfunction "D6_8") (pintype "passive"))
      (node (ref "RN2") (pin "10") (pinfunction "10_10") (pintype "passive"))
    )
    (net (code "62") (name "Net-(IC3-D7)") (class "Default")
      (node (ref "IC3") (pin "9") (pinfunction "D7_9") (pintype "passive"))
      (node (ref "RN2") (pin "9") (pinfunction "9_9") (pintype "passive"))
    )
    (net (code "63") (name "Net-(IC3-Q0)") (class "Default")
      (node (ref "IC3") (pin "19") (pinfunction "Q0_19") (pintype "passive"))
      (node (ref "RN4") (pin "1") (pinfunction "1_1") (pintype "passive"))
    )
    (net (code "64") (name "Net-(IC3-Q1)") (class "Default")
      (node (ref "IC3") (pin "18") (pinfunction "Q1_18") (pintype "passive"))
      (node (ref "RN4") (pin "2") (pinfunction "2_2") (pintype "passive"))
    )
    (net (code "65") (name "Net-(IC3-Q2)") (class "Default")
      (node (ref "IC3") (pin "17") (pinfunction "Q2_17") (pintype "passive"))
      (node (ref "RN4") (pin "3") (pinfunction "3_3") (pintype "passive"))
    )
    (net (code "66") (name "Net-(IC3-Q3)") (class "Default")
      (node (ref "IC3") (pin "16") (pinfunction "Q3_16") (pintype "passive"))
      (node (ref "RN4") (pin "4") (pinfunction "4_4") (pintype "passive"))
    )
    (net (code "67") (name "Net-(IC3-Q4)") (class "Default")
      (node (ref "IC3") (pin "15") (pinfunction "Q4_15") (pintype "passive"))
      (node (ref "RN4") (pin "5") (pinfunction "5_5") (pintype "passive"))
    )
    (net (code "68") (name "Net-(IC3-Q5)") (class "Default")
      (node (ref "IC3") (pin "14") (pinfunction "Q5_14") (pintype "passive"))
      (node (ref "RN4") (pin "6") (pinfunction "6_6") (pintype "passive"))
    )
    (net (code "69") (name "Net-(IC3-Q6)") (class "Default")
      (node (ref "IC3") (pin "13") (pinfunction "Q6_13") (pintype "passive"))
      (node (ref "RN4") (pin "7") (pinfunction "7_7") (pintype "passive"))
    )
    (net (code "70") (name "Net-(IC3-Q7)") (class "Default")
      (node (ref "IC3") (pin "12") (pinfunction "Q7_12") (pintype "passive"))
      (node (ref "RN4") (pin "8") (pinfunction "8_8") (pintype "passive"))
    )
    (net (code "71") (name "Net-(LD1-A)") (class "Default")
      (node (ref "LD1") (pin "1") (pinfunction "A_1") (pintype "passive"))
      (node (ref "R5") (pin "2") (pintype "passive"))
    )
    (net (code "72") (name "Net-(LD2-A)") (class "Default")
      (node (ref "LD2") (pin "1") (pinfunction "A_1") (pintype "passive"))
      (node (ref "R6") (pin "2") (pintype "passive"))
    )
    (net (code "73") (name "Net-(P1-X)") (class "Default")
      (node (ref "P1") (pin "1") (pinfunction "X_1") (pintype "passive"))
      (node (ref "R1") (pin "2") (pintype "passive"))
      (node (ref "T1") (pin "1") (pinfunction "PRIMARY_1") (pintype "passive"))
    )
    (net (code "74") (name "Net-(T1-SECONDARY)") (class "Default")
      (node (ref "R2") (pin "1") (pintype "passive"))
      (node (ref "T1") (pin "6") (pinfunction "SECONDARY_6") (pintype "passive"))
    )
    (net (code "75") (name "Net-(T1-SECONDARY_CT)") (class "Default")
      (node (ref "C24") (pin "1") (pintype "passive"))
      (node (ref "T1") (pin "5") (pinfunction "SECONDARY_CT_5") (pintype "passive"))
    )
    (net (code "76") (name "Net-(T1-SECONDARY_DOT)") (class "Default")
      (node (ref "R3") (pin "1") (pintype "passive"))
      (node (ref "T1") (pin "4") (pinfunction "SECONDARY_DOT_4") (pintype "passive"))
    )
    (net (code "77") (name "Net-(T2-SECONDARY)") (class "Default")
      (node (ref "D1") (pin "3") (pintype "passive"))
      (node (ref "T2") (pin "6") (pinfunction "SECONDARY_6") (pintype "passive"))
      (node (ref "U1") (pin "6") (pinfunction "*ENCODE_6") (pintype "input"))
    )
    (net (code "78") (name "Net-(T2-SECONDARY_CT)") (class "Default")
      (node (ref "C25") (pin "1") (pintype "passive"))
      (node (ref "T2") (pin "5") (pinfunction "SECONDARY_CT_5") (pintype "passive"))
    )
    (net (code "79") (name "Net-(T2-SECONDARY_DOT)") (class "Default")
      (node (ref "D1") (pin "1") (pintype "passive"))
      (node (ref "D1") (pin "2") (pintype "passive"))
      (node (ref "T2") (pin "4") (pinfunction "SECONDARY_DOT_4") (pintype "passive"))
      (node (ref "U1") (pin "5") (pinfunction "ENCODE_5") (pintype "input"))
    )
    (net (code "80") (name "Net-(U1A-C1)") (class "Default")
      (node (ref "C1") (pin "1") (pintype "passive"))
      (node (ref "U1") (pin "20") (pinfunction "C1_20") (pintype "passive"))
    )
    (net (code "81") (name "Net-(U1A-C2)") (class "Default")
      (node (ref "C2") (pin "1") (pintype "passive"))
      (node (ref "U1") (pin "24") (pinfunction "C2_24") (pintype "passive"))
    )
    (net (code "82") (name "Net-(U4-NR)") (class "Default")
      (node (ref "C5") (pin "2") (pintype "passive"))
      (node (ref "U4") (pin "14") (pinfunction "NR_14") (pintype "input"))
    )
    (net (code "83") (name "Net-(U5-NR)") (class "Default")
      (node (ref "C15") (pin "2") (pintype "passive"))
      (node (ref "U5") (pin "14") (pinfunction "NR_14") (pintype "input"))
    )
    (net (code "84") (name "VCC") (class "Default")
      (node (ref "C13") (pin "2") (pintype "passive"))
      (node (ref "C14") (pin "2") (pintype "passive"))
      (node (ref "C3") (pin "2") (pintype "passive"))
      (node (ref "C4") (pin "2") (pintype "passive"))
      (node (ref "P3") (pin "1") (pinfunction "1_1") (pintype "passive"))
      (node (ref "P4") (pin "2") (pinfunction "2_2") (pintype "passive"))
      (node (ref "U4") (pin "13") (pinfunction "EN_13") (pintype "input"))
      (node (ref "U4") (pin "15") (pinfunction "IN_15") (pintype "power_in"))
      (node (ref "U4") (pin "16") (pinfunction "IN_16") (pintype "power_in"))
      (node (ref "U5") (pin "13") (pinfunction "EN_13") (pintype "input"))
      (node (ref "U5") (pin "15") (pinfunction "IN_15") (pintype "power_in"))
      (node (ref "U5") (pin "16") (pinfunction "IN_16") (pintype "power_in"))
    )
    (net (code "85") (name "VREF") (class "Default")
      (node (ref "C23") (pin "2") (pintype "passive"))
      (node (ref "U1") (pin "3") (pinfunction "VREF_3") (pintype "power_in"))
    )
    (net (code "86") (name "unconnected-(RN2-Pad1)") (class "Default")
      (node (ref "RN2") (pin "1") (pinfunction "1_1") (pintype "passive"))
    )
    (net (code "87") (name "unconnected-(RN4-Pad16)") (class "Default")
      (node (ref "RN4") (pin "16") (pinfunction "16_16") (pintype "passive"))
    )
    (net (code "88") (name "unconnected-(T1-NOT_USED-Pad2)") (class "Default")
      (node (ref "T1") (pin "2") (pinfunction "NOT_USED_2") (pintype "passive+no_connect"))
    )
    (net (code "89") (name "unconnected-(T2-NOT_USED-Pad2)") (class "Default")
      (node (ref "T2") (pin "2") (pinfunction "NOT_USED_2") (pintype "passive+no_connect"))
    )
    (net (code "90") (name "unconnected-(U1A-DMID-Pad35)") (class "Default")
      (node (ref "U1") (pin "35") (pinfunction "DMID_35") (pintype "output+no_connect"))
    )
    (net (code "91") (name "unconnected-(U1B-DNC-Pad31)") (class "Default")
      (node (ref "U1") (pin "31") (pinfunction "DNC_31") (pintype "passive+no_connect"))
    )
    (net (code "92") (name "unconnected-(U4-0P1V-Pad12)") (class "Default")
      (node (ref "U4") (pin "12") (pinfunction "0P1V_12") (pintype "passive+no_connect"))
    )
    (net (code "93") (name "unconnected-(U4-0P2V-Pad11)") (class "Default")
      (node (ref "U4") (pin "11") (pinfunction "0P2V_11") (pintype "passive+no_connect"))
    )
    (net (code "94") (name "unconnected-(U4-0P8V-Pad9)") (class "Default")
      (node (ref "U4") (pin "9") (pinfunction "0P8V_9") (pintype "passive+no_connect"))
    )
    (net (code "95") (name "unconnected-(U4-1P6V-Pad8)") (class "Default")
      (node (ref "U4") (pin "8") (pinfunction "1P6V_8") (pintype "passive+no_connect"))
    )
    (net (code "96") (name "unconnected-(U4-6P4V1-Pad5)") (class "Default")
      (node (ref "U4") (pin "5") (pinfunction "6P4V1_5") (pintype "passive+no_connect"))
    )
    (net (code "97") (name "unconnected-(U4-6P4V2-Pad4)") (class "Default")
      (node (ref "U4") (pin "4") (pinfunction "6P4V2_4") (pintype "passive+no_connect"))
    )
    (net (code "98") (name "unconnected-(U4-NC-Pad2)") (class "Default")
      (node (ref "U4") (pin "2") (pinfunction "NC_2") (pintype "passive+no_connect"))
    )
    (net (code "99") (name "unconnected-(U4-NC-Pad17)") (class "Default")
      (node (ref "U4") (pin "17") (pinfunction "NC_17") (pintype "passive+no_connect"))
    )
    (net (code "100") (name "unconnected-(U4-NC-Pad18)") (class "Default")
      (node (ref "U4") (pin "18") (pinfunction "NC_18") (pintype "passive+no_connect"))
    )
    (net (code "101") (name "unconnected-(U4-NC-Pad19)") (class "Default")
      (node (ref "U4") (pin "19") (pinfunction "NC_19") (pintype "passive+no_connect"))
    )
    (net (code "102") (name "unconnected-(U5-0P4V-Pad10)") (class "Default")
      (node (ref "U5") (pin "10") (pinfunction "0P4V_10") (pintype "passive+no_connect"))
    )
    (net (code "103") (name "unconnected-(U5-0P8V-Pad9)") (class "Default")
      (node (ref "U5") (pin "9") (pinfunction "0P8V_9") (pintype "passive+no_connect"))
    )
    (net (code "104") (name "unconnected-(U5-3P2V-Pad6)") (class "Default")
      (node (ref "U5") (pin "6") (pinfunction "3P2V_6") (pintype "passive+no_connect"))
    )
    (net (code "105") (name "unconnected-(U5-6P4V1-Pad5)") (class "Default")
      (node (ref "U5") (pin "5") (pinfunction "6P4V1_5") (pintype "passive+no_connect"))
    )
    (net (code "106") (name "unconnected-(U5-6P4V2-Pad4)") (class "Default")
      (node (ref "U5") (pin "4") (pinfunction "6P4V2_4") (pintype "passive+no_connect"))
    )
    (net (code "107") (name "unconnected-(U5-NC-Pad2)") (class "Default")
      (node (ref "U5") (pin "2") (pinfunction "NC_2") (pintype "passive+no_connect"))
    )
    (net (code "108") (name "unconnected-(U5-NC-Pad17)") (class "Default")
      (node (ref "U5") (pin "17") (pinfunction "NC_17") (pintype "passive+no_connect"))
    )
    (net (code "109") (name "unconnected-(U5-NC-Pad18)") (class "Default")
      (node (ref "U5") (pin "18") (pinfunction "NC_18") (pintype "passive+no_connect"))
    )
    (net (code "110") (name "unconnected-(U5-NC-Pad19)") (class "Default")
      (node (ref "U5") (pin "19") (pinfunction "NC_19") (pintype "passive+no_connect"))
    )
  )
)
